# hd6303-mb-ram-rom-x1-ext-dec.net
KiCad netlist of a schematic drawn in EAGLE
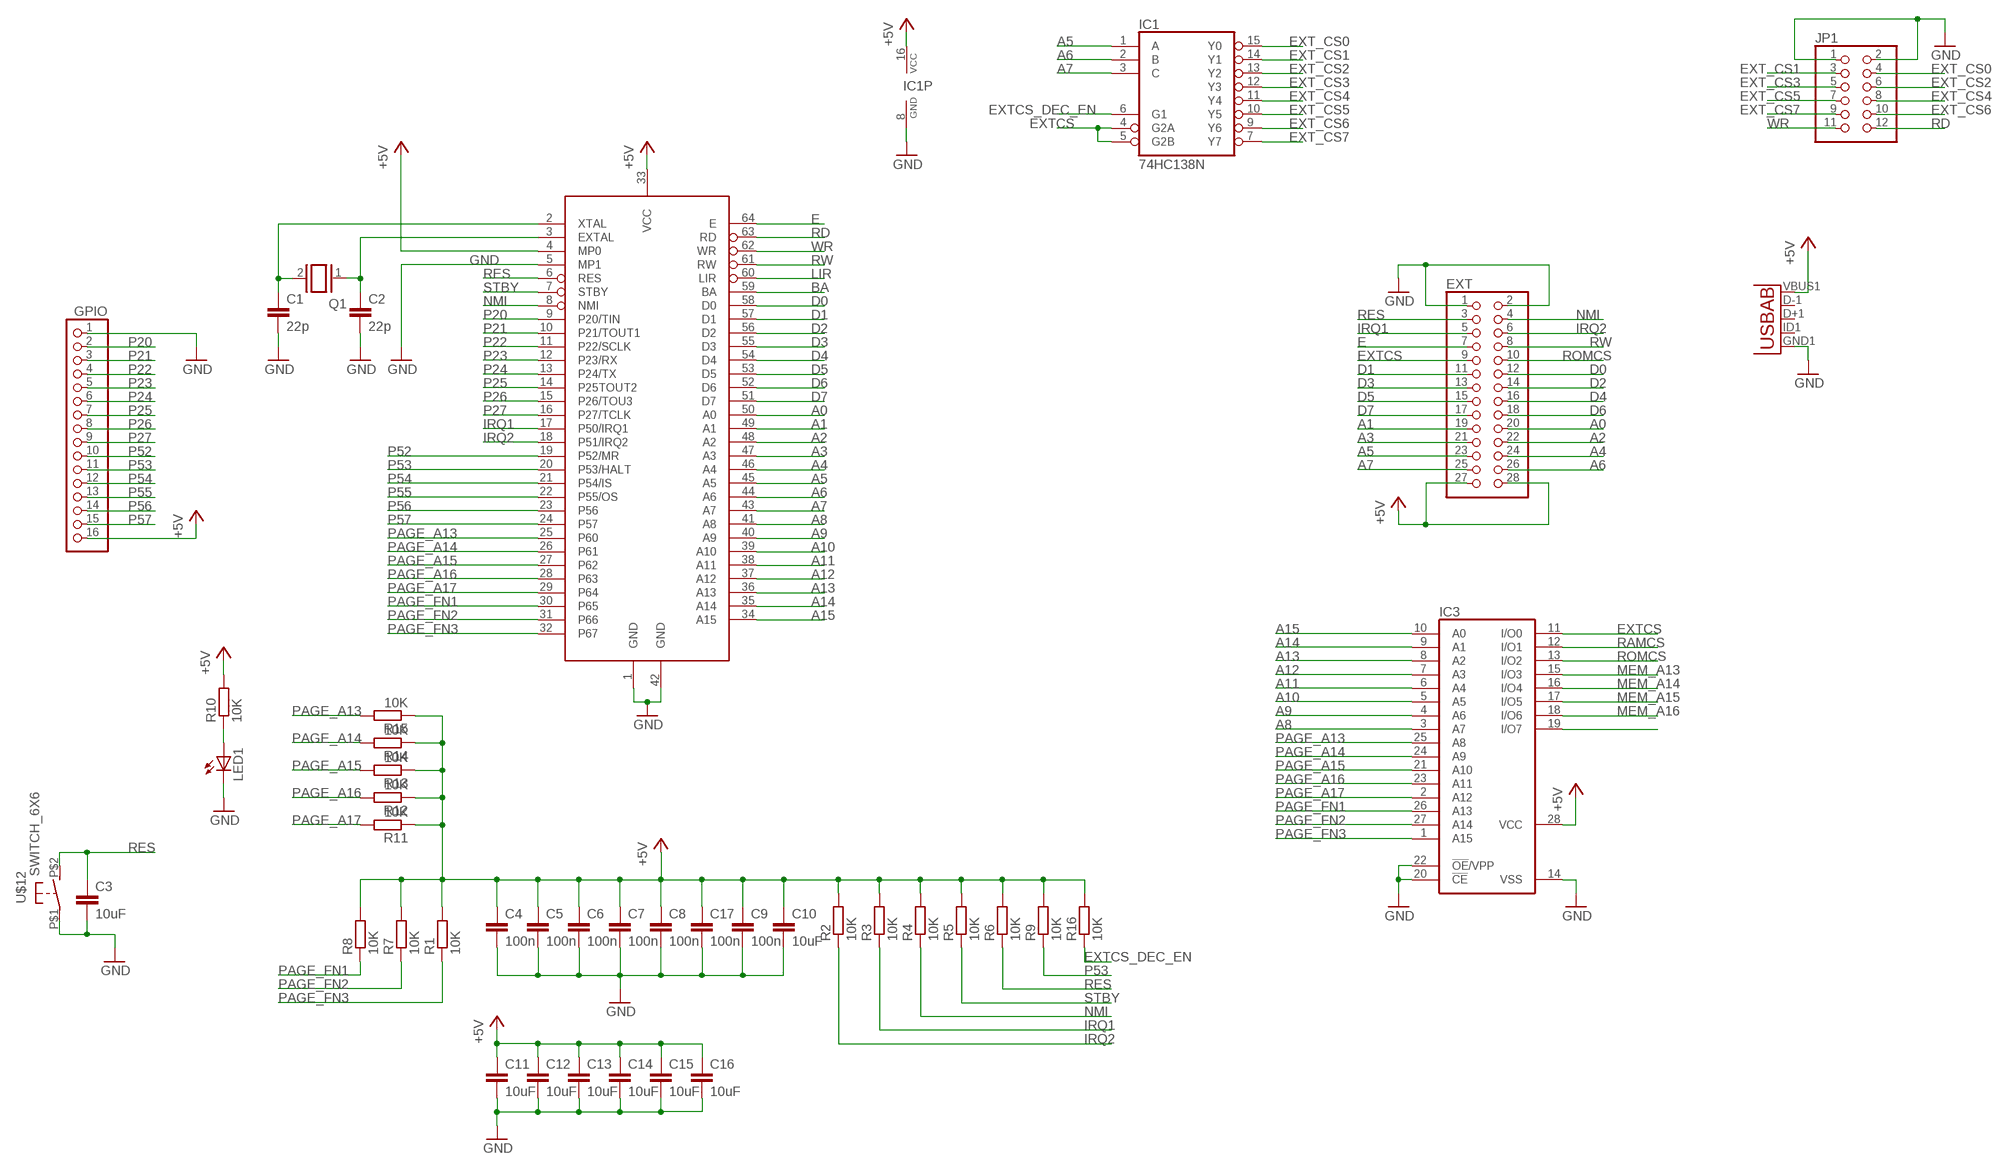
[diagram p0: schematic, sheet 1]
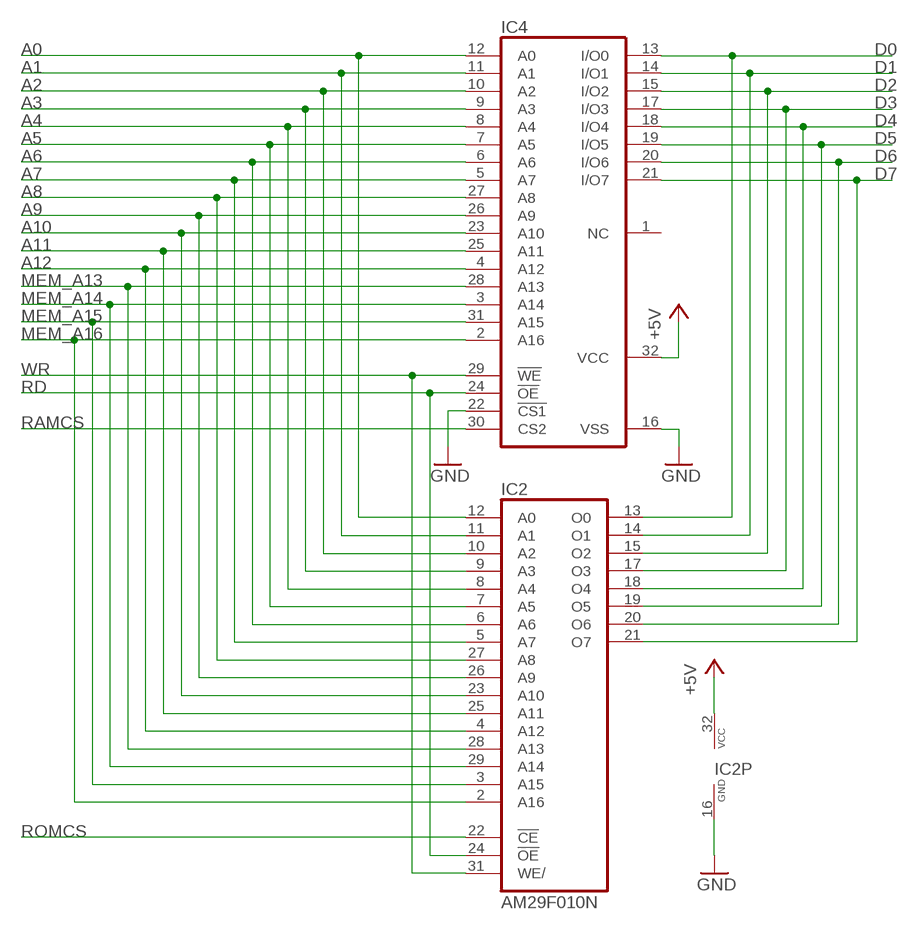
[diagram p1: schematic, sheet 2]

(export (version "E")
  (design (tool "Eeschema 10.0.6"))
  (components
    (comp (ref "IC2")
      (value "AM29F010N")
      (footprint "eagle-import:DIP32")
      (libsource (lib "eagle-import") (part "AM29F010N"))
    )
    (comp (ref "IC4")
      (value "628128P")
      (footprint "eagle-import:DIL32")
      (libsource (lib "eagle-import") (part "628128P"))
    )
    (comp (ref "C1")
      (value "22p")
      (footprint "eagle-import:C0603")
      (libsource (lib "eagle-import") (part "rcl_334_C-EUC0603"))
    )
    (comp (ref "C2")
      (value "22p")
      (footprint "eagle-import:C0603")
      (libsource (lib "eagle-import") (part "C-EUC0603"))
    )
    (comp (ref "C3")
      (value "10uF")
      (footprint "eagle-import:C0805")
      (libsource (lib "eagle-import") (part "resistor_348_C-EUC0805"))
    )
    (comp (ref "C4")
      (value "100n")
      (footprint "eagle-import:C0603")
      (libsource (lib "eagle-import") (part "C-EUC0603"))
    )
    (comp (ref "C5")
      (value "100n")
      (footprint "eagle-import:C0603")
      (libsource (lib "eagle-import") (part "C-EUC0603"))
    )
    (comp (ref "C6")
      (value "100n")
      (footprint "eagle-import:C0603")
      (libsource (lib "eagle-import") (part "C-EUC0603"))
    )
    (comp (ref "C7")
      (value "100n")
      (footprint "eagle-import:C0603")
      (libsource (lib "eagle-import") (part "C-EUC0603"))
    )
    (comp (ref "C8")
      (value "100n")
      (footprint "eagle-import:C0603")
      (libsource (lib "eagle-import") (part "C-EUC0603"))
    )
    (comp (ref "C9")
      (value "100n")
      (footprint "eagle-import:C0603")
      (libsource (lib "eagle-import") (part "C-EUC0603"))
    )
    (comp (ref "C10")
      (value "10uF")
      (footprint "eagle-import:C0805")
      (libsource (lib "eagle-import") (part "resistor_348_C-EUC0805"))
    )
    (comp (ref "C11")
      (value "10uF")
      (footprint "eagle-import:C0805")
      (libsource (lib "eagle-import") (part "resistor_348_C-EUC0805"))
    )
    (comp (ref "C12")
      (value "10uF")
      (footprint "eagle-import:C0805")
      (libsource (lib "eagle-import") (part "resistor_348_C-EUC0805"))
    )
    (comp (ref "C13")
      (value "10uF")
      (footprint "eagle-import:C0805")
      (libsource (lib "eagle-import") (part "resistor_348_C-EUC0805"))
    )
    (comp (ref "C14")
      (value "10uF")
      (footprint "eagle-import:C0805")
      (libsource (lib "eagle-import") (part "resistor_348_C-EUC0805"))
    )
    (comp (ref "C15")
      (value "10uF")
      (footprint "eagle-import:C0805")
      (libsource (lib "eagle-import") (part "resistor_348_C-EUC0805"))
    )
    (comp (ref "C16")
      (value "10uF")
      (footprint "eagle-import:C0805")
      (libsource (lib "eagle-import") (part "resistor_348_C-EUC0805"))
    )
    (comp (ref "C17")
      (value "100n")
      (footprint "eagle-import:C0603")
      (libsource (lib "eagle-import") (part "C-EUC0603"))
    )
    (comp (ref "EXT")
      (value "PINHD-2X14")
      (footprint "eagle-import:2X14")
      (libsource (lib "eagle-import") (part "PINHD-2X14"))
    )
    (comp (ref "GPIO")
      (value "PINHD-1X16")
      (footprint "eagle-import:1X16")
      (libsource (lib "eagle-import") (part "PINHD-1X16"))
    )
    (comp (ref "IC1")
      (value "74HC138N")
      (footprint "eagle-import:DIL16")
      (libsource (lib "eagle-import") (part "74138NHC"))
    )
    (comp (ref "IC3")
      (value "27512G")
      (footprint "eagle-import:DIL28-6")
      (libsource (lib "eagle-import") (part "27512G"))
    )
    (comp (ref "JP1")
      (value "PINHD-2X6")
      (footprint "eagle-import:2X06")
      (libsource (lib "eagle-import") (part "PINHD-2X6"))
    )
    (comp (ref "LED1")
      (value "LED5MM")
      (footprint "eagle-import:LED5MM")
      (libsource (lib "eagle-import") (part "LED5MM"))
    )
    (comp (ref "Q1")
      (value "XTAL/S")
      (footprint "eagle-import:QS")
      (libsource (lib "eagle-import") (part "XTAL/S"))
    )
    (comp (ref "R1")
      (value "10K")
      (footprint "eagle-import:R0603")
      (libsource (lib "eagle-import") (part "R-EU_R0603"))
    )
    (comp (ref "R2")
      (value "10K")
      (footprint "eagle-import:R0603")
      (libsource (lib "eagle-import") (part "R-EU_R0603"))
    )
    (comp (ref "R3")
      (value "10K")
      (footprint "eagle-import:R0603")
      (libsource (lib "eagle-import") (part "R-EU_R0603"))
    )
    (comp (ref "R4")
      (value "10K")
      (footprint "eagle-import:R0603")
      (libsource (lib "eagle-import") (part "R-EU_R0603"))
    )
    (comp (ref "R5")
      (value "10K")
      (footprint "eagle-import:R0603")
      (libsource (lib "eagle-import") (part "R-EU_R0603"))
    )
    (comp (ref "R6")
      (value "10K")
      (footprint "eagle-import:R0603")
      (libsource (lib "eagle-import") (part "R-EU_R0603"))
    )
    (comp (ref "R7")
      (value "10K")
      (footprint "eagle-import:R0603")
      (libsource (lib "eagle-import") (part "R-EU_R0603"))
    )
    (comp (ref "R8")
      (value "10K")
      (footprint "eagle-import:R0603")
      (libsource (lib "eagle-import") (part "R-EU_R0603"))
    )
    (comp (ref "R9")
      (value "10K")
      (footprint "eagle-import:R0603")
      (libsource (lib "eagle-import") (part "R-EU_R0603"))
    )
    (comp (ref "R10")
      (value "10K")
      (footprint "eagle-import:R0603")
      (libsource (lib "eagle-import") (part "R-EU_R0603"))
    )
    (comp (ref "R11")
      (value "10K")
      (footprint "eagle-import:R0603")
      (libsource (lib "eagle-import") (part "R-EU_R0603"))
    )
    (comp (ref "R12")
      (value "10K")
      (footprint "eagle-import:R0603")
      (libsource (lib "eagle-import") (part "R-EU_R0603"))
    )
    (comp (ref "R13")
      (value "10K")
      (footprint "eagle-import:R0603")
      (libsource (lib "eagle-import") (part "R-EU_R0603"))
    )
    (comp (ref "R14")
      (value "10K")
      (footprint "eagle-import:R0603")
      (libsource (lib "eagle-import") (part "R-EU_R0603"))
    )
    (comp (ref "R15")
      (value "10K")
      (footprint "eagle-import:R0603")
      (libsource (lib "eagle-import") (part "R-EU_R0603"))
    )
    (comp (ref "R16")
      (value "10K")
      (footprint "eagle-import:R0603")
      (libsource (lib "eagle-import") (part "R-EU_R0603"))
    )
    (comp (ref "U$1")
      (value "HD6303YCP")
      (footprint "eagle-import:DP-64S")
      (libsource (lib "eagle-import") (part "HD6303YCP"))
    )
    (comp (ref "U$12")
      (value "SWITCH_6X6")
      (footprint "eagle-import:SWITCH_6X6")
      (libsource (lib "eagle-import") (part "SWITCH_6X6"))
    )
    (comp (ref "U2")
      (value "USB\"\"")
      (footprint "eagle-import:USB-MICRO-SMD")
      (libsource (lib "eagle-import") (part "USB{dblquote}{dblquote}"))
    )
  )
  (nets
    (net (code "1") (name "+5V") (class "Default")
      (node (ref "C10") (pin "1") (pinfunction "1_1") (pintype "passive"))
      (node (ref "C11") (pin "1") (pinfunction "1_1") (pintype "passive"))
      (node (ref "C12") (pin "1") (pinfunction "1_1") (pintype "passive"))
      (node (ref "C13") (pin "1") (pinfunction "1_1") (pintype "passive"))
      (node (ref "C14") (pin "1") (pinfunction "1_1") (pintype "passive"))
      (node (ref "C15") (pin "1") (pinfunction "1_1") (pintype "passive"))
      (node (ref "C16") (pin "1") (pinfunction "1_1") (pintype "passive"))
      (node (ref "C17") (pin "1") (pinfunction "1_1") (pintype "passive"))
      (node (ref "C4") (pin "1") (pinfunction "1_1") (pintype "passive"))
      (node (ref "C5") (pin "1") (pinfunction "1_1") (pintype "passive"))
      (node (ref "C6") (pin "1") (pinfunction "1_1") (pintype "passive"))
      (node (ref "C7") (pin "1") (pinfunction "1_1") (pintype "passive"))
      (node (ref "C8") (pin "1") (pinfunction "1_1") (pintype "passive"))
      (node (ref "C9") (pin "1") (pinfunction "1_1") (pintype "passive"))
      (node (ref "EXT") (pin "27") (pinfunction "27_27") (pintype "passive"))
      (node (ref "EXT") (pin "28") (pinfunction "28_28") (pintype "passive"))
      (node (ref "GPIO") (pin "16") (pinfunction "16_16") (pintype "passive"))
      (node (ref "IC1") (pin "16") (pinfunction "VCC_16") (pintype "power_in"))
      (node (ref "IC2") (pin "32") (pinfunction "VCC_32") (pintype "power_in"))
      (node (ref "IC3") (pin "28") (pinfunction "VCC_28") (pintype "power_in"))
      (node (ref "IC4") (pin "32") (pinfunction "VCC_32") (pintype "power_in"))
      (node (ref "R1") (pin "2") (pinfunction "2_2") (pintype "passive"))
      (node (ref "R10") (pin "2") (pinfunction "2_2") (pintype "passive"))
      (node (ref "R11") (pin "1") (pinfunction "1_1") (pintype "passive"))
      (node (ref "R12") (pin "1") (pinfunction "1_1") (pintype "passive"))
      (node (ref "R13") (pin "1") (pinfunction "1_1") (pintype "passive"))
      (node (ref "R14") (pin "1") (pinfunction "1_1") (pintype "passive"))
      (node (ref "R15") (pin "1") (pinfunction "1_1") (pintype "passive"))
      (node (ref "R16") (pin "2") (pinfunction "2_2") (pintype "passive"))
      (node (ref "R2") (pin "2") (pinfunction "2_2") (pintype "passive"))
      (node (ref "R3") (pin "2") (pinfunction "2_2") (pintype "passive"))
      (node (ref "R4") (pin "2") (pinfunction "2_2") (pintype "passive"))
      (node (ref "R5") (pin "2") (pinfunction "2_2") (pintype "passive"))
      (node (ref "R6") (pin "2") (pinfunction "2_2") (pintype "passive"))
      (node (ref "R7") (pin "2") (pinfunction "2_2") (pintype "passive"))
      (node (ref "R8") (pin "2") (pinfunction "2_2") (pintype "passive"))
      (node (ref "R9") (pin "2") (pinfunction "2_2") (pintype "passive"))
      (node (ref "U$1") (pin "33") (pinfunction "VCC_33") (pintype "power_in"))
      (node (ref "U$1") (pin "4") (pinfunction "MP0_4") (pintype "input"))
      (node (ref "U2") (pin "VBUS1") (pinfunction "VBUS_VBUS1") (pintype "bidirectional"))
    )
    (net (code "2") (name "A0") (class "Default")
      (node (ref "EXT") (pin "20") (pinfunction "20_20") (pintype "passive"))
      (node (ref "IC2") (pin "12") (pinfunction "A0_12") (pintype "input"))
      (node (ref "IC4") (pin "12") (pinfunction "A0_12") (pintype "input"))
      (node (ref "U$1") (pin "50") (pinfunction "A0_50") (pintype "output"))
    )
    (net (code "3") (name "A1") (class "Default")
      (node (ref "EXT") (pin "19") (pinfunction "19_19") (pintype "passive"))
      (node (ref "IC2") (pin "11") (pinfunction "A1_11") (pintype "input"))
      (node (ref "IC4") (pin "11") (pinfunction "A1_11") (pintype "input"))
      (node (ref "U$1") (pin "49") (pinfunction "A1_49") (pintype "output"))
    )
    (net (code "4") (name "A2") (class "Default")
      (node (ref "EXT") (pin "22") (pinfunction "22_22") (pintype "passive"))
      (node (ref "IC2") (pin "10") (pinfunction "A2_10") (pintype "input"))
      (node (ref "IC4") (pin "10") (pinfunction "A2_10") (pintype "input"))
      (node (ref "U$1") (pin "48") (pinfunction "A2_48") (pintype "output"))
    )
    (net (code "5") (name "A3") (class "Default")
      (node (ref "EXT") (pin "21") (pinfunction "21_21") (pintype "passive"))
      (node (ref "IC2") (pin "9") (pinfunction "A3_9") (pintype "input"))
      (node (ref "IC4") (pin "9") (pinfunction "A3_9") (pintype "input"))
      (node (ref "U$1") (pin "47") (pinfunction "A3_47") (pintype "output"))
    )
    (net (code "6") (name "A4") (class "Default")
      (node (ref "EXT") (pin "24") (pinfunction "24_24") (pintype "passive"))
      (node (ref "IC2") (pin "8") (pinfunction "A4_8") (pintype "input"))
      (node (ref "IC4") (pin "8") (pinfunction "A4_8") (pintype "input"))
      (node (ref "U$1") (pin "46") (pinfunction "A4_46") (pintype "output"))
    )
    (net (code "7") (name "A5") (class "Default")
      (node (ref "EXT") (pin "23") (pinfunction "23_23") (pintype "passive"))
      (node (ref "IC1") (pin "1") (pinfunction "A_1") (pintype "input"))
      (node (ref "IC2") (pin "7") (pinfunction "A5_7") (pintype "input"))
      (node (ref "IC4") (pin "7") (pinfunction "A5_7") (pintype "input"))
      (node (ref "U$1") (pin "45") (pinfunction "A5_45") (pintype "output"))
    )
    (net (code "8") (name "A6") (class "Default")
      (node (ref "EXT") (pin "26") (pinfunction "26_26") (pintype "passive"))
      (node (ref "IC1") (pin "2") (pinfunction "B_2") (pintype "input"))
      (node (ref "IC2") (pin "6") (pinfunction "A6_6") (pintype "input"))
      (node (ref "IC4") (pin "6") (pinfunction "A6_6") (pintype "input"))
      (node (ref "U$1") (pin "44") (pinfunction "A6_44") (pintype "output"))
    )
    (net (code "9") (name "A7") (class "Default")
      (node (ref "EXT") (pin "25") (pinfunction "25_25") (pintype "passive"))
      (node (ref "IC1") (pin "3") (pinfunction "C_3") (pintype "input"))
      (node (ref "IC2") (pin "5") (pinfunction "A7_5") (pintype "input"))
      (node (ref "IC4") (pin "5") (pinfunction "A7_5") (pintype "input"))
      (node (ref "U$1") (pin "43") (pinfunction "A7_43") (pintype "output"))
    )
    (net (code "10") (name "A8") (class "Default")
      (node (ref "IC2") (pin "27") (pinfunction "A8_27") (pintype "input"))
      (node (ref "IC3") (pin "3") (pinfunction "A7_3") (pintype "input"))
      (node (ref "IC4") (pin "27") (pinfunction "A8_27") (pintype "input"))
      (node (ref "U$1") (pin "41") (pinfunction "A8_41") (pintype "output"))
    )
    (net (code "11") (name "A9") (class "Default")
      (node (ref "IC2") (pin "26") (pinfunction "A9_26") (pintype "input"))
      (node (ref "IC3") (pin "4") (pinfunction "A6_4") (pintype "input"))
      (node (ref "IC4") (pin "26") (pinfunction "A9_26") (pintype "input"))
      (node (ref "U$1") (pin "40") (pinfunction "A9_40") (pintype "output"))
    )
    (net (code "12") (name "A10") (class "Default")
      (node (ref "IC2") (pin "23") (pinfunction "A10_23") (pintype "input"))
      (node (ref "IC3") (pin "5") (pinfunction "A5_5") (pintype "input"))
      (node (ref "IC4") (pin "23") (pinfunction "A10_23") (pintype "input"))
      (node (ref "U$1") (pin "39") (pinfunction "A10_39") (pintype "output"))
    )
    (net (code "13") (name "A11") (class "Default")
      (node (ref "IC2") (pin "25") (pinfunction "A11_25") (pintype "input"))
      (node (ref "IC3") (pin "6") (pinfunction "A4_6") (pintype "input"))
      (node (ref "IC4") (pin "25") (pinfunction "A11_25") (pintype "input"))
      (node (ref "U$1") (pin "38") (pinfunction "A11_38") (pintype "output"))
    )
    (net (code "14") (name "A12") (class "Default")
      (node (ref "IC2") (pin "4") (pinfunction "A12_4") (pintype "input"))
      (node (ref "IC3") (pin "7") (pinfunction "A3_7") (pintype "input"))
      (node (ref "IC4") (pin "4") (pinfunction "A12_4") (pintype "input"))
      (node (ref "U$1") (pin "37") (pinfunction "A12_37") (pintype "output"))
    )
    (net (code "15") (name "A13") (class "Default")
      (node (ref "IC3") (pin "8") (pinfunction "A2_8") (pintype "input"))
      (node (ref "U$1") (pin "36") (pinfunction "A13_36") (pintype "output"))
    )
    (net (code "16") (name "A14") (class "Default")
      (node (ref "IC3") (pin "9") (pinfunction "A1_9") (pintype "input"))
      (node (ref "U$1") (pin "35") (pinfunction "A14_35") (pintype "output"))
    )
    (net (code "17") (name "A15") (class "Default")
      (node (ref "IC3") (pin "10") (pinfunction "A0_10") (pintype "input"))
      (node (ref "U$1") (pin "34") (pinfunction "A15_34") (pintype "output"))
    )
    (net (code "18") (name "BA") (class "Default")
      (node (ref "U$1") (pin "59") (pinfunction "BA_59") (pintype "output"))
    )
    (net (code "19") (name "D0") (class "Default")
      (node (ref "EXT") (pin "12") (pinfunction "12_12") (pintype "passive"))
      (node (ref "IC2") (pin "13") (pinfunction "O0_13") (pintype "tri_state"))
      (node (ref "IC4") (pin "13") (pinfunction "I/O0_13") (pintype "bidirectional"))
      (node (ref "U$1") (pin "58") (pinfunction "D0_58") (pintype "bidirectional"))
    )
    (net (code "20") (name "D1") (class "Default")
      (node (ref "EXT") (pin "11") (pinfunction "11_11") (pintype "passive"))
      (node (ref "IC2") (pin "14") (pinfunction "O1_14") (pintype "tri_state"))
      (node (ref "IC4") (pin "14") (pinfunction "I/O1_14") (pintype "bidirectional"))
      (node (ref "U$1") (pin "57") (pinfunction "D1_57") (pintype "bidirectional"))
    )
    (net (code "21") (name "D2") (class "Default")
      (node (ref "EXT") (pin "14") (pinfunction "14_14") (pintype "passive"))
      (node (ref "IC2") (pin "15") (pinfunction "O2_15") (pintype "tri_state"))
      (node (ref "IC4") (pin "15") (pinfunction "I/O2_15") (pintype "bidirectional"))
      (node (ref "U$1") (pin "56") (pinfunction "D2_56") (pintype "bidirectional"))
    )
    (net (code "22") (name "D3") (class "Default")
      (node (ref "EXT") (pin "13") (pinfunction "13_13") (pintype "passive"))
      (node (ref "IC2") (pin "17") (pinfunction "O3_17") (pintype "tri_state"))
      (node (ref "IC4") (pin "17") (pinfunction "I/O3_17") (pintype "bidirectional"))
      (node (ref "U$1") (pin "55") (pinfunction "D3_55") (pintype "bidirectional"))
    )
    (net (code "23") (name "D4") (class "Default")
      (node (ref "EXT") (pin "16") (pinfunction "16_16") (pintype "passive"))
      (node (ref "IC2") (pin "18") (pinfunction "O4_18") (pintype "tri_state"))
      (node (ref "IC4") (pin "18") (pinfunction "I/O4_18") (pintype "bidirectional"))
      (node (ref "U$1") (pin "54") (pinfunction "D4_54") (pintype "bidirectional"))
    )
    (net (code "24") (name "D5") (class "Default")
      (node (ref "EXT") (pin "15") (pinfunction "15_15") (pintype "passive"))
      (node (ref "IC2") (pin "19") (pinfunction "O5_19") (pintype "tri_state"))
      (node (ref "IC4") (pin "19") (pinfunction "I/O5_19") (pintype "bidirectional"))
      (node (ref "U$1") (pin "53") (pinfunction "D5_53") (pintype "bidirectional"))
    )
    (net (code "25") (name "D6") (class "Default")
      (node (ref "EXT") (pin "18") (pinfunction "18_18") (pintype "passive"))
      (node (ref "IC2") (pin "20") (pinfunction "O6_20") (pintype "tri_state"))
      (node (ref "IC4") (pin "20") (pinfunction "I/O6_20") (pintype "bidirectional"))
      (node (ref "U$1") (pin "52") (pinfunction "D6_52") (pintype "bidirectional"))
    )
    (net (code "26") (name "D7") (class "Default")
      (node (ref "EXT") (pin "17") (pinfunction "17_17") (pintype "passive"))
      (node (ref "IC2") (pin "21") (pinfunction "O7_21") (pintype "tri_state"))
      (node (ref "IC4") (pin "21") (pinfunction "I/O7_21") (pintype "bidirectional"))
      (node (ref "U$1") (pin "51") (pinfunction "D7_51") (pintype "bidirectional"))
    )
    (net (code "27") (name "E") (class "Default")
      (node (ref "EXT") (pin "7") (pinfunction "7_7") (pintype "passive"))
      (node (ref "U$1") (pin "64") (pinfunction "E_64") (pintype "output"))
    )
    (net (code "28") (name "EXTCS") (class "Default")
      (node (ref "EXT") (pin "9") (pinfunction "9_9") (pintype "passive"))
      (node (ref "IC1") (pin "4") (pinfunction "G2A_4") (pintype "input"))
      (node (ref "IC1") (pin "5") (pinfunction "G2B_5") (pintype "input"))
      (node (ref "IC3") (pin "11") (pinfunction "I/O0_11") (pintype "tri_state"))
    )
    (net (code "29") (name "EXTCS_DEC_EN") (class "Default")
      (node (ref "IC1") (pin "6") (pinfunction "G1_6") (pintype "input"))
      (node (ref "R16") (pin "1") (pinfunction "1_1") (pintype "passive"))
    )
    (net (code "30") (name "EXT_CS0") (class "Default")
      (node (ref "IC1") (pin "15") (pinfunction "Y0_15") (pintype "output"))
      (node (ref "JP1") (pin "4") (pinfunction "4_4") (pintype "passive"))
    )
    (net (code "31") (name "EXT_CS1") (class "Default")
      (node (ref "IC1") (pin "14") (pinfunction "Y1_14") (pintype "output"))
      (node (ref "JP1") (pin "3") (pinfunction "3_3") (pintype "passive"))
    )
    (net (code "32") (name "EXT_CS2") (class "Default")
      (node (ref "IC1") (pin "13") (pinfunction "Y2_13") (pintype "output"))
      (node (ref "JP1") (pin "6") (pinfunction "6_6") (pintype "passive"))
    )
    (net (code "33") (name "EXT_CS3") (class "Default")
      (node (ref "IC1") (pin "12") (pinfunction "Y3_12") (pintype "output"))
      (node (ref "JP1") (pin "5") (pinfunction "5_5") (pintype "passive"))
    )
    (net (code "34") (name "EXT_CS4") (class "Default")
      (node (ref "IC1") (pin "11") (pinfunction "Y4_11") (pintype "output"))
      (node (ref "JP1") (pin "8") (pinfunction "8_8") (pintype "passive"))
    )
    (net (code "35") (name "EXT_CS5") (class "Default")
      (node (ref "IC1") (pin "10") (pinfunction "Y5_10") (pintype "output"))
      (node (ref "JP1") (pin "7") (pinfunction "7_7") (pintype "passive"))
    )
    (net (code "36") (name "EXT_CS6") (class "Default")
      (node (ref "IC1") (pin "9") (pinfunction "Y6_9") (pintype "output"))
      (node (ref "JP1") (pin "10") (pinfunction "10_10") (pintype "passive"))
    )
    (net (code "37") (name "EXT_CS7") (class "Default")
      (node (ref "IC1") (pin "7") (pinfunction "Y7_7") (pintype "output"))
      (node (ref "JP1") (pin "9") (pinfunction "9_9") (pintype "passive"))
    )
    (net (code "38") (name "GND") (class "Default")
      (node (ref "C1") (pin "2") (pinfunction "2_2") (pintype "passive"))
      (node (ref "C10") (pin "2") (pinfunction "2_2") (pintype "passive"))
      (node (ref "C11") (pin "2") (pinfunction "2_2") (pintype "passive"))
      (node (ref "C12") (pin "2") (pinfunction "2_2") (pintype "passive"))
      (node (ref "C13") (pin "2") (pinfunction "2_2") (pintype "passive"))
      (node (ref "C14") (pin "2") (pinfunction "2_2") (pintype "passive"))
      (node (ref "C15") (pin "2") (pinfunction "2_2") (pintype "passive"))
      (node (ref "C16") (pin "2") (pinfunction "2_2") (pintype "passive"))
      (node (ref "C17") (pin "2") (pinfunction "2_2") (pintype "passive"))
      (node (ref "C2") (pin "2") (pinfunction "2_2") (pintype "passive"))
      (node (ref "C3") (pin "2") (pinfunction "2_2") (pintype "passive"))
      (node (ref "C4") (pin "2") (pinfunction "2_2") (pintype "passive"))
      (node (ref "C5") (pin "2") (pinfunction "2_2") (pintype "passive"))
      (node (ref "C6") (pin "2") (pinfunction "2_2") (pintype "passive"))
      (node (ref "C7") (pin "2") (pinfunction "2_2") (pintype "passive"))
      (node (ref "C8") (pin "2") (pinfunction "2_2") (pintype "passive"))
      (node (ref "C9") (pin "2") (pinfunction "2_2") (pintype "passive"))
      (node (ref "EXT") (pin "1") (pinfunction "1_1") (pintype "passive"))
      (node (ref "EXT") (pin "2") (pinfunction "2_2") (pintype "passive"))
      (node (ref "GPIO") (pin "1") (pinfunction "1_1") (pintype "passive"))
      (node (ref "IC1") (pin "8") (pinfunction "GND_8") (pintype "power_in"))
      (node (ref "IC2") (pin "16") (pinfunction "GND_16") (pintype "power_in"))
      (node (ref "IC3") (pin "14") (pinfunction "VSS_14") (pintype "power_in"))
      (node (ref "IC3") (pin "20") (pinfunction "~{CE}_20") (pintype "input"))
      (node (ref "IC3") (pin "22") (pinfunction "~{OE}/VPP_22") (pintype "input"))
      (node (ref "IC4") (pin "16") (pinfunction "VSS_16") (pintype "power_in"))
      (node (ref "IC4") (pin "22") (pinfunction "~{CS1}_22") (pintype "input"))
      (node (ref "JP1") (pin "1") (pinfunction "1_1") (pintype "passive"))
      (node (ref "JP1") (pin "2") (pinfunction "2_2") (pintype "passive"))
      (node (ref "LED1") (pin "K") (pinfunction "C_K") (pintype "passive"))
      (node (ref "U$1") (pin "1") (pinfunction "GND_1") (pintype "power_in"))
      (node (ref "U$1") (pin "42") (pinfunction "GND_42") (pintype "power_in"))
      (node (ref "U$1") (pin "5") (pinfunction "MP1_5") (pintype "input"))
      (node (ref "U$12") (pin "P$1") (pinfunction "P_P$1") (pintype "passive"))
      (node (ref "U2") (pin "GND1") (pinfunction "GND_GND1") (pintype "bidirectional"))
    )
    (net (code "39") (name "IRQ1") (class "Default")
      (node (ref "EXT") (pin "5") (pinfunction "5_5") (pintype "passive"))
      (node (ref "R3") (pin "1") (pinfunction "1_1") (pintype "passive"))
      (node (ref "U$1") (pin "17") (pinfunction "P50/IRQ1_17") (pintype "bidirectional"))
    )
    (net (code "40") (name "IRQ2") (class "Default")
      (node (ref "EXT") (pin "6") (pinfunction "6_6") (pintype "passive"))
      (node (ref "R2") (pin "1") (pinfunction "1_1") (pintype "passive"))
      (node (ref "U$1") (pin "18") (pinfunction "P51/IRQ2_18") (pintype "bidirectional"))
    )
    (net (code "41") (name "LIR") (class "Default")
      (node (ref "U$1") (pin "60") (pinfunction "LIR_60") (pintype "output"))
    )
    (net (code "42") (name "MEM_A13") (class "Default")
      (node (ref "IC2") (pin "28") (pinfunction "A13_28") (pintype "input"))
      (node (ref "IC3") (pin "15") (pinfunction "I/O3_15") (pintype "tri_state"))
      (node (ref "IC4") (pin "28") (pinfunction "A13_28") (pintype "input"))
    )
    (net (code "43") (name "MEM_A14") (class "Default")
      (node (ref "IC2") (pin "29") (pinfunction "A14_29") (pintype "input"))
      (node (ref "IC3") (pin "16") (pinfunction "I/O4_16") (pintype "tri_state"))
      (node (ref "IC4") (pin "3") (pinfunction "A14_3") (pintype "input"))
    )
    (net (code "44") (name "MEM_A15") (class "Default")
      (node (ref "IC2") (pin "3") (pinfunction "A15_3") (pintype "input"))
      (node (ref "IC3") (pin "17") (pinfunction "I/O5_17") (pintype "tri_state"))
      (node (ref "IC4") (pin "31") (pinfunction "A15_31") (pintype "input"))
    )
    (net (code "45") (name "MEM_A16") (class "Default")
      (node (ref "IC2") (pin "2") (pinfunction "A16_2") (pintype "input"))
      (node (ref "IC3") (pin "18") (pinfunction "I/O6_18") (pintype "tri_state"))
      (node (ref "IC4") (pin "2") (pinfunction "A16_2") (pintype "input"))
    )
    (net (code "46") (name "NMI") (class "Default")
      (node (ref "EXT") (pin "4") (pinfunction "4_4") (pintype "passive"))
      (node (ref "R4") (pin "1") (pinfunction "1_1") (pintype "passive"))
      (node (ref "U$1") (pin "8") (pinfunction "NMI_8") (pintype "input"))
    )
    (net (code "47") (name "Net-(LED1-PadA)") (class "Default")
      (node (ref "LED1") (pin "A") (pinfunction "A_A") (pintype "passive"))
      (node (ref "R10") (pin "1") (pinfunction "1_1") (pintype "passive"))
    )
    (net (code "48") (name "Net-(U$1-EXTAL)") (class "Default")
      (node (ref "C2") (pin "1") (pinfunction "1_1") (pintype "passive"))
      (node (ref "Q1") (pin "1") (pinfunction "1_1") (pintype "passive"))
      (node (ref "U$1") (pin "3") (pinfunction "EXTAL_3") (pintype "input"))
    )
    (net (code "49") (name "Net-(U$1-XTAL)") (class "Default")
      (node (ref "C1") (pin "1") (pinfunction "1_1") (pintype "passive"))
      (node (ref "Q1") (pin "2") (pinfunction "2_2") (pintype "passive"))
      (node (ref "U$1") (pin "2") (pinfunction "XTAL_2") (pintype "input"))
    )
    (net (code "50") (name "P20") (class "Default")
      (node (ref "GPIO") (pin "2") (pinfunction "2_2") (pintype "passive"))
      (node (ref "U$1") (pin "9") (pinfunction "P20/TIN_9") (pintype "bidirectional"))
    )
    (net (code "51") (name "P21") (class "Default")
      (node (ref "GPIO") (pin "3") (pinfunction "3_3") (pintype "passive"))
      (node (ref "U$1") (pin "10") (pinfunction "P21/TOUT1_10") (pintype "bidirectional"))
    )
    (net (code "52") (name "P22") (class "Default")
      (node (ref "GPIO") (pin "4") (pinfunction "4_4") (pintype "passive"))
      (node (ref "U$1") (pin "11") (pinfunction "P22/SCLK_11") (pintype "bidirectional"))
    )
    (net (code "53") (name "P23") (class "Default")
      (node (ref "GPIO") (pin "5") (pinfunction "5_5") (pintype "passive"))
      (node (ref "U$1") (pin "12") (pinfunction "P23/RX_12") (pintype "bidirectional"))
    )
    (net (code "54") (name "P24") (class "Default")
      (node (ref "GPIO") (pin "6") (pinfunction "6_6") (pintype "passive"))
      (node (ref "U$1") (pin "13") (pinfunction "P24/TX_13") (pintype "bidirectional"))
    )
    (net (code "55") (name "P25") (class "Default")
      (node (ref "GPIO") (pin "7") (pinfunction "7_7") (pintype "passive"))
      (node (ref "U$1") (pin "14") (pinfunction "P25TOUT2_14") (pintype "bidirectional"))
    )
    (net (code "56") (name "P26") (class "Default")
      (node (ref "GPIO") (pin "8") (pinfunction "8_8") (pintype "passive"))
      (node (ref "U$1") (pin "15") (pinfunction "P26/TOU3_15") (pintype "bidirectional"))
    )
    (net (code "57") (name "P27") (class "Default")
      (node (ref "GPIO") (pin "9") (pinfunction "9_9") (pintype "passive"))
      (node (ref "U$1") (pin "16") (pinfunction "P27/TCLK_16") (pintype "bidirectional"))
    )
    (net (code "58") (name "P52") (class "Default")
      (node (ref "GPIO") (pin "10") (pinfunction "10_10") (pintype "passive"))
      (node (ref "U$1") (pin "19") (pinfunction "P52/MR_19") (pintype "bidirectional"))
    )
    (net (code "59") (name "P53") (class "Default")
      (node (ref "GPIO") (pin "11") (pinfunction "11_11") (pintype "passive"))
      (node (ref "R9") (pin "1") (pinfunction "1_1") (pintype "passive"))
      (node (ref "U$1") (pin "20") (pinfunction "P53/HALT_20") (pintype "bidirectional"))
    )
    (net (code "60") (name "P54") (class "Default")
      (node (ref "GPIO") (pin "12") (pinfunction "12_12") (pintype "passive"))
      (node (ref "U$1") (pin "21") (pinfunction "P54/IS_21") (pintype "bidirectional"))
    )
    (net (code "61") (name "P55") (class "Default")
      (node (ref "GPIO") (pin "13") (pinfunction "13_13") (pintype "passive"))
      (node (ref "U$1") (pin "22") (pinfunction "P55/OS_22") (pintype "bidirectional"))
    )
    (net (code "62") (name "P56") (class "Default")
      (node (ref "GPIO") (pin "14") (pinfunction "14_14") (pintype "passive"))
      (node (ref "U$1") (pin "23") (pinfunction "P56_23") (pintype "bidirectional"))
    )
    (net (code "63") (name "P57") (class "Default")
      (node (ref "GPIO") (pin "15") (pinfunction "15_15") (pintype "passive"))
      (node (ref "U$1") (pin "24") (pinfunction "P57_24") (pintype "bidirectional"))
    )
    (net (code "64") (name "PAGE_A13") (class "Default")
      (node (ref "IC3") (pin "25") (pinfunction "A8_25") (pintype "input"))
      (node (ref "R15") (pin "2") (pinfunction "2_2") (pintype "passive"))
      (node (ref "U$1") (pin "25") (pinfunction "P60_25") (pintype "bidirectional"))
    )
    (net (code "65") (name "PAGE_A14") (class "Default")
      (node (ref "IC3") (pin "24") (pinfunction "A9_24") (pintype "input"))
      (node (ref "R14") (pin "2") (pinfunction "2_2") (pintype "passive"))
      (node (ref "U$1") (pin "26") (pinfunction "P61_26") (pintype "bidirectional"))
    )
    (net (code "66") (name "PAGE_A15") (class "Default")
      (node (ref "IC3") (pin "21") (pinfunction "A10_21") (pintype "input"))
      (node (ref "R13") (pin "2") (pinfunction "2_2") (pintype "passive"))
      (node (ref "U$1") (pin "27") (pinfunction "P62_27") (pintype "bidirectional"))
    )
    (net (code "67") (name "PAGE_A16") (class "Default")
      (node (ref "IC3") (pin "23") (pinfunction "A11_23") (pintype "input"))
      (node (ref "R12") (pin "2") (pinfunction "2_2") (pintype "passive"))
      (node (ref "U$1") (pin "28") (pinfunction "P63_28") (pintype "bidirectional"))
    )
    (net (code "68") (name "PAGE_A17") (class "Default")
      (node (ref "IC3") (pin "2") (pinfunction "A12_2") (pintype "input"))
      (node (ref "R11") (pin "2") (pinfunction "2_2") (pintype "passive"))
      (node (ref "U$1") (pin "29") (pinfunction "P64_29") (pintype "bidirectional"))
    )
    (net (code "69") (name "PAGE_FN1") (class "Default")
      (node (ref "IC3") (pin "26") (pinfunction "A13_26") (pintype "input"))
      (node (ref "R8") (pin "1") (pinfunction "1_1") (pintype "passive"))
      (node (ref "U$1") (pin "30") (pinfunction "P65_30") (pintype "bidirectional"))
    )
    (net (code "70") (name "PAGE_FN2") (class "Default")
      (node (ref "IC3") (pin "27") (pinfunction "A14_27") (pintype "input"))
      (node (ref "R7") (pin "1") (pinfunction "1_1") (pintype "passive"))
      (node (ref "U$1") (pin "31") (pinfunction "P66_31") (pintype "bidirectional"))
    )
    (net (code "71") (name "PAGE_FN3") (class "Default")
      (node (ref "IC3") (pin "1") (pinfunction "A15_1") (pintype "input"))
      (node (ref "R1") (pin "1") (pinfunction "1_1") (pintype "passive"))
      (node (ref "U$1") (pin "32") (pinfunction "P67_32") (pintype "bidirectional"))
    )
    (net (code "72") (name "RAMCS") (class "Default")
      (node (ref "IC3") (pin "12") (pinfunction "I/O1_12") (pintype "tri_state"))
      (node (ref "IC4") (pin "30") (pinfunction "CS2_30") (pintype "input"))
    )
    (net (code "73") (name "RD") (class "Default")
      (node (ref "IC2") (pin "24") (pinfunction "~{OE}_24") (pintype "input"))
      (node (ref "IC4") (pin "24") (pinfunction "~{OE}_24") (pintype "input"))
      (node (ref "JP1") (pin "12") (pinfunction "12_12") (pintype "passive"))
      (node (ref "U$1") (pin "63") (pinfunction "RD_63") (pintype "output"))
    )
    (net (code "74") (name "RES") (class "Default")
      (node (ref "C3") (pin "1") (pinfunction "1_1") (pintype "passive"))
      (node (ref "EXT") (pin "3") (pinfunction "3_3") (pintype "passive"))
      (node (ref "R6") (pin "1") (pinfunction "1_1") (pintype "passive"))
      (node (ref "U$1") (pin "6") (pinfunction "RES_6") (pintype "input"))
      (node (ref "U$12") (pin "P$2") (pinfunction "S_P$2") (pintype "passive"))
    )
    (net (code "75") (name "ROMCS") (class "Default")
      (node (ref "EXT") (pin "10") (pinfunction "10_10") (pintype "passive"))
      (node (ref "IC2") (pin "22") (pinfunction "~{CE}_22") (pintype "input"))
      (node (ref "IC3") (pin "13") (pinfunction "I/O2_13") (pintype "tri_state"))
    )
    (net (code "76") (name "RW") (class "Default")
      (node (ref "EXT") (pin "8") (pinfunction "8_8") (pintype "passive"))
      (node (ref "U$1") (pin "61") (pinfunction "RW_61") (pintype "output"))
    )
    (net (code "77") (name "STBY") (class "Default")
      (node (ref "R5") (pin "1") (pinfunction "1_1") (pintype "passive"))
      (node (ref "U$1") (pin "7") (pinfunction "STBY_7") (pintype "input"))
    )
    (net (code "78") (name "WR") (class "Default")
      (node (ref "IC2") (pin "31") (pinfunction "WE/_31") (pintype "input"))
      (node (ref "IC4") (pin "29") (pinfunction "~{WE}_29") (pintype "input"))
      (node (ref "JP1") (pin "11") (pinfunction "11_11") (pintype "passive"))
      (node (ref "U$1") (pin "62") (pinfunction "WR_62") (pintype "output"))
    )
    (net (code "79") (name "unconnected-(IC3-I{slash}O7-Pad19)") (class "Default")
      (node (ref "IC3") (pin "19") (pinfunction "I/O7_19") (pintype "tri_state"))
    )
    (net (code "80") (name "unconnected-(IC4-NC-Pad1)") (class "Default")
      (node (ref "IC4") (pin "1") (pinfunction "NC_1") (pintype "no_connect"))
    )
    (net (code "81") (name "unconnected-(U2-D+-PadD+1)") (class "Default")
      (node (ref "U2") (pin "D+1") (pinfunction "D+_D+1") (pintype "bidirectional"))
    )
    (net (code "82") (name "unconnected-(U2-D--PadD-1)") (class "Default")
      (node (ref "U2") (pin "D-1") (pinfunction "D-_D-1") (pintype "bidirectional"))
    )
    (net (code "83") (name "unconnected-(U2-USBID-PadID1)") (class "Default")
      (node (ref "U2") (pin "ID1") (pinfunction "USBID_ID1") (pintype "bidirectional"))
    )
  )
)
